# sts30-dis-breakout.net
KiCad netlist of a schematic drawn in EAGLE
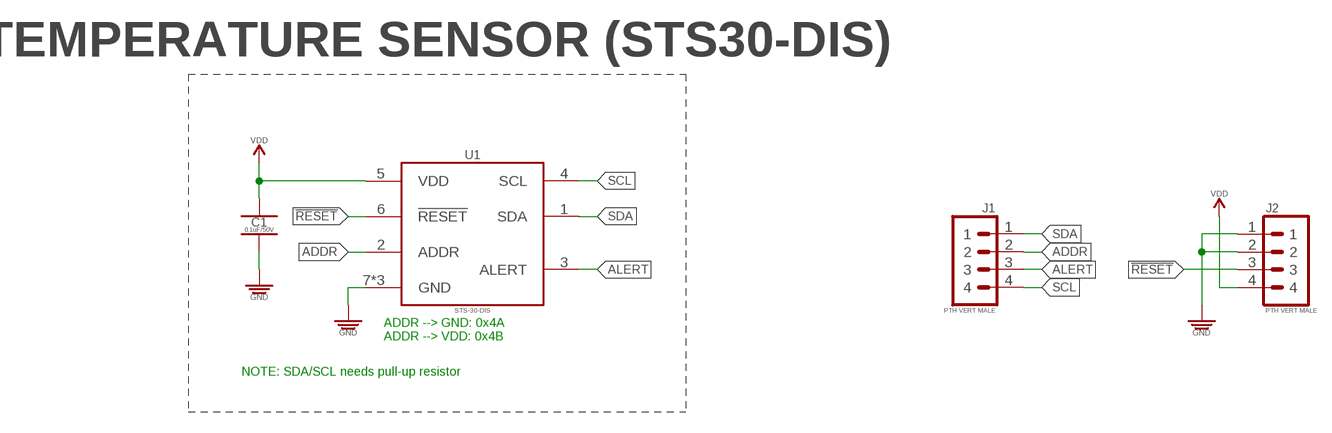
[diagram p0: schematic, sheet 1]

(export (version "E")
  (design (tool "Eeschema 10.0.6"))
  (components
    (comp (ref "C1")
      (value "0.1uF/50V")
      (footprint "eagle-import:CAPC1005X55_SMD-0402")
      (fields (field (name "MFR") "TDK Corporation") (field (name "MPN") "C1005X7R1H104K050BE"))
      (libsource (lib "eagle-import") (part "0.1UF_SMD-0402_50V-10%"))
    )
    (comp (ref "J1")
      (value "PTH VERT MALE")
      (footprint "eagle-import:HDRV4W64P254_1X4_1016X254X838B")
      (fields (field (name "MFR") "Sullins Connector Solutions") (field (name "MPN") "PEC04SAAN"))
      (libsource (lib "eagle-import") (part "1X04_PTH_VERT_MALE_2.54MM"))
    )
    (comp (ref "J2")
      (value "PTH VERT MALE")
      (footprint "eagle-import:HDRV4W64P254_1X4_1016X254X838B")
      (fields (field (name "MFR") "Sullins Connector Solutions") (field (name "MPN") "PEC04SAAN"))
      (libsource (lib "eagle-import") (part "1X04_PTH_VERT_MALE_2.54MM"))
    )
    (comp (ref "U1")
      (value "STS-30-DIS")
      (footprint "eagle-import:SON50P250X250X100-9T110X180N")
      (fields (field (name "MFR") "Sensirion AG"))
      (libsource (lib "eagle-import") (part "STS3X-DISSTS30-DIS"))
    )
  )
  (nets
    (net (code "1") (name "/~{RESET}") (class "Default")
      (node (ref "J2") (pin "3") (pinfunction "3_3") (pintype "passive"))
      (node (ref "U1") (pin "6") (pinfunction "~{RESET}_6") (pintype "bidirectional"))
    )
    (net (code "2") (name "ADDR") (class "Default")
      (node (ref "J1") (pin "2") (pinfunction "2_2") (pintype "passive"))
      (node (ref "U1") (pin "2") (pinfunction "ADDR_2") (pintype "bidirectional"))
    )
    (net (code "3") (name "ALERT") (class "Default")
      (node (ref "J1") (pin "3") (pinfunction "3_3") (pintype "passive"))
      (node (ref "U1") (pin "3") (pinfunction "ALERT_3") (pintype "bidirectional"))
    )
    (net (code "4") (name "GND") (class "Default")
      (node (ref "C1") (pin "2") (pinfunction "2_2") (pintype "passive"))
      (node (ref "J2") (pin "1") (pinfunction "1_1") (pintype "passive"))
      (node (ref "J2") (pin "2") (pinfunction "2_2") (pintype "passive"))
      (node (ref "U1") (pin "7") (pinfunction "GND_7") (pintype "power_in"))
      (node (ref "U1") (pin "8") (pinfunction "GND_8") (pintype "power_in"))
      (node (ref "U1") (pin "9") (pinfunction "GND_9") (pintype "power_in"))
    )
    (net (code "5") (name "SCL") (class "Default")
      (node (ref "J1") (pin "4") (pinfunction "4_4") (pintype "passive"))
      (node (ref "U1") (pin "4") (pinfunction "SCL_4") (pintype "bidirectional"))
    )
    (net (code "6") (name "SDA") (class "Default")
      (node (ref "J1") (pin "1") (pinfunction "1_1") (pintype "passive"))
      (node (ref "U1") (pin "1") (pinfunction "SDA_1") (pintype "bidirectional"))
    )
    (net (code "7") (name "VDD") (class "Default")
      (node (ref "C1") (pin "1") (pinfunction "1_1") (pintype "passive"))
      (node (ref "J2") (pin "4") (pinfunction "4_4") (pintype "passive"))
      (node (ref "U1") (pin "5") (pinfunction "VDD_5") (pintype "power_in"))
    )
  )
)
